# quad_l293d.net
KiCad netlist of a schematic drawn in EAGLE
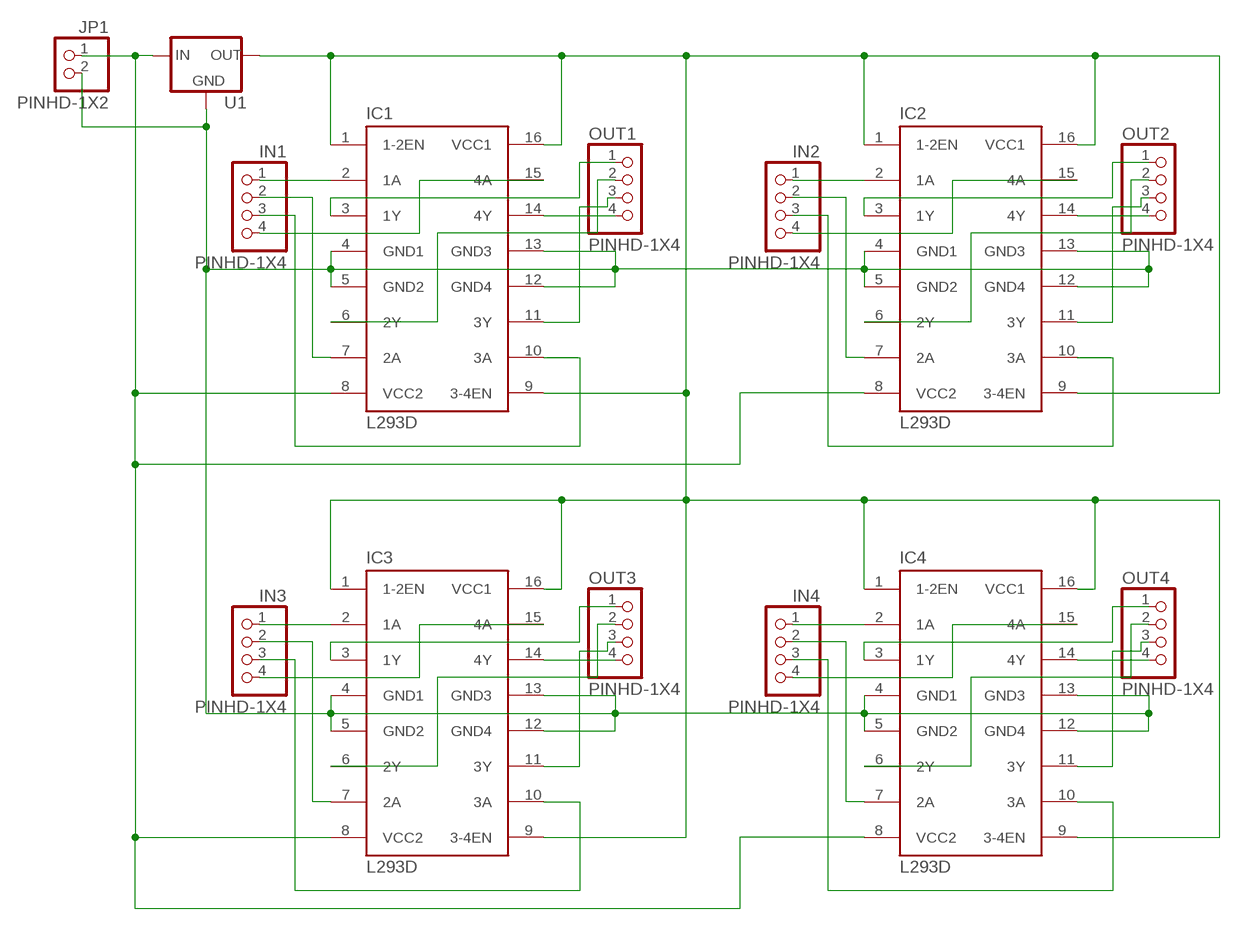
[diagram p0: schematic, sheet 1]

(export (version "E")
  (design (tool "Eeschema 10.0.6"))
  (components
    (comp (ref "IC1")
      (value "L293D")
      (footprint "eagle-import:DIL16")
      (libsource (lib "eagle-import") (part "L293D"))
    )
    (comp (ref "IC2")
      (value "L293D")
      (footprint "eagle-import:DIL16")
      (libsource (lib "eagle-import") (part "L293D"))
    )
    (comp (ref "IC3")
      (value "L293D")
      (footprint "eagle-import:DIL16")
      (libsource (lib "eagle-import") (part "L293D"))
    )
    (comp (ref "IC4")
      (value "L293D")
      (footprint "eagle-import:DIL16")
      (libsource (lib "eagle-import") (part "L293D"))
    )
    (comp (ref "IN1")
      (value "PINHD-1X4")
      (footprint "eagle-import:1X04")
      (libsource (lib "eagle-import") (part "PINHD-1X4"))
    )
    (comp (ref "IN2")
      (value "PINHD-1X4")
      (footprint "eagle-import:1X04")
      (libsource (lib "eagle-import") (part "PINHD-1X4"))
    )
    (comp (ref "IN3")
      (value "PINHD-1X4")
      (footprint "eagle-import:1X04")
      (libsource (lib "eagle-import") (part "PINHD-1X4"))
    )
    (comp (ref "IN4")
      (value "PINHD-1X4")
      (footprint "eagle-import:1X04")
      (libsource (lib "eagle-import") (part "PINHD-1X4"))
    )
    (comp (ref "JP1")
      (value "PINHD-1X2")
      (footprint "eagle-import:1X02")
      (libsource (lib "eagle-import") (part "PINHD-1X2"))
    )
    (comp (ref "OUT1")
      (value "PINHD-1X4")
      (footprint "eagle-import:1X04")
      (libsource (lib "eagle-import") (part "PINHD-1X4"))
    )
    (comp (ref "OUT2")
      (value "PINHD-1X4")
      (footprint "eagle-import:1X04")
      (libsource (lib "eagle-import") (part "PINHD-1X4"))
    )
    (comp (ref "OUT3")
      (value "PINHD-1X4")
      (footprint "eagle-import:1X04")
      (libsource (lib "eagle-import") (part "PINHD-1X4"))
    )
    (comp (ref "OUT4")
      (value "PINHD-1X4")
      (footprint "eagle-import:1X04")
      (libsource (lib "eagle-import") (part "PINHD-1X4"))
    )
    (comp (ref "U1")
      (value "V_REG_78XX-TO-220")
      (footprint "eagle-import:TO-220-ALT")
      (libsource (lib "eagle-import") (part "V_REG_78XX-TO-220"))
    )
  )
  (nets
    (net (code "1") (name "Net-(IC1-1-2EN)") (class "Default")
      (node (ref "IC1") (pin "1") (pinfunction "1-2EN_1") (pintype "input"))
      (node (ref "IC1") (pin "16") (pinfunction "VCC1_16") (pintype "power_in"))
      (node (ref "IC1") (pin "9") (pinfunction "3-4EN_9") (pintype "input"))
      (node (ref "IC2") (pin "1") (pinfunction "1-2EN_1") (pintype "input"))
      (node (ref "IC2") (pin "16") (pinfunction "VCC1_16") (pintype "power_in"))
      (node (ref "IC2") (pin "9") (pinfunction "3-4EN_9") (pintype "input"))
      (node (ref "IC3") (pin "1") (pinfunction "1-2EN_1") (pintype "input"))
      (node (ref "IC3") (pin "16") (pinfunction "VCC1_16") (pintype "power_in"))
      (node (ref "IC3") (pin "9") (pinfunction "3-4EN_9") (pintype "input"))
      (node (ref "IC4") (pin "1") (pinfunction "1-2EN_1") (pintype "input"))
      (node (ref "IC4") (pin "16") (pinfunction "VCC1_16") (pintype "power_in"))
      (node (ref "IC4") (pin "9") (pinfunction "3-4EN_9") (pintype "input"))
      (node (ref "U1") (pin "OUT") (pinfunction "OUT_OUT") (pintype "passive"))
    )
    (net (code "2") (name "Net-(IC1-1A)") (class "Default")
      (node (ref "IC1") (pin "2") (pinfunction "1A_2") (pintype "input"))
      (node (ref "IN1") (pin "1") (pinfunction "1_1") (pintype "passive"))
    )
    (net (code "3") (name "Net-(IC1-1Y)") (class "Default")
      (node (ref "IC1") (pin "3") (pinfunction "1Y_3") (pintype "output"))
      (node (ref "OUT1") (pin "1") (pinfunction "1_1") (pintype "passive"))
    )
    (net (code "4") (name "Net-(IC1-2A)") (class "Default")
      (node (ref "IC1") (pin "7") (pinfunction "2A_7") (pintype "input"))
      (node (ref "IN1") (pin "2") (pinfunction "2_2") (pintype "passive"))
    )
    (net (code "5") (name "Net-(IC1-2Y)") (class "Default")
      (node (ref "IC1") (pin "6") (pinfunction "2Y_6") (pintype "output"))
      (node (ref "OUT1") (pin "2") (pinfunction "2_2") (pintype "passive"))
    )
    (net (code "6") (name "Net-(IC1-3A)") (class "Default")
      (node (ref "IC1") (pin "10") (pinfunction "3A_10") (pintype "input"))
      (node (ref "IN1") (pin "3") (pinfunction "3_3") (pintype "passive"))
    )
    (net (code "7") (name "Net-(IC1-3Y)") (class "Default")
      (node (ref "IC1") (pin "11") (pinfunction "3Y_11") (pintype "output"))
      (node (ref "OUT1") (pin "3") (pinfunction "3_3") (pintype "passive"))
    )
    (net (code "8") (name "Net-(IC1-4A)") (class "Default")
      (node (ref "IC1") (pin "15") (pinfunction "4A_15") (pintype "input"))
      (node (ref "IN1") (pin "4") (pinfunction "4_4") (pintype "passive"))
    )
    (net (code "9") (name "Net-(IC1-4Y)") (class "Default")
      (node (ref "IC1") (pin "14") (pinfunction "4Y_14") (pintype "output"))
      (node (ref "OUT1") (pin "4") (pinfunction "4_4") (pintype "passive"))
    )
    (net (code "10") (name "Net-(IC1-GND1)") (class "Default")
      (node (ref "IC1") (pin "12") (pinfunction "GND4_12") (pintype "power_in"))
      (node (ref "IC1") (pin "13") (pinfunction "GND3_13") (pintype "power_in"))
      (node (ref "IC1") (pin "4") (pinfunction "GND1_4") (pintype "power_in"))
      (node (ref "IC1") (pin "5") (pinfunction "GND2_5") (pintype "power_in"))
      (node (ref "IC2") (pin "12") (pinfunction "GND4_12") (pintype "power_in"))
      (node (ref "IC2") (pin "13") (pinfunction "GND3_13") (pintype "power_in"))
      (node (ref "IC2") (pin "4") (pinfunction "GND1_4") (pintype "power_in"))
      (node (ref "IC2") (pin "5") (pinfunction "GND2_5") (pintype "power_in"))
      (node (ref "IC3") (pin "12") (pinfunction "GND4_12") (pintype "power_in"))
      (node (ref "IC3") (pin "13") (pinfunction "GND3_13") (pintype "power_in"))
      (node (ref "IC3") (pin "4") (pinfunction "GND1_4") (pintype "power_in"))
      (node (ref "IC3") (pin "5") (pinfunction "GND2_5") (pintype "power_in"))
      (node (ref "IC4") (pin "12") (pinfunction "GND4_12") (pintype "power_in"))
      (node (ref "IC4") (pin "13") (pinfunction "GND3_13") (pintype "power_in"))
      (node (ref "IC4") (pin "4") (pinfunction "GND1_4") (pintype "power_in"))
      (node (ref "IC4") (pin "5") (pinfunction "GND2_5") (pintype "power_in"))
      (node (ref "JP1") (pin "2") (pinfunction "2_2") (pintype "passive"))
      (node (ref "U1") (pin "GND") (pinfunction "GND_GND") (pintype "input"))
    )
    (net (code "11") (name "Net-(IC1-VCC2)") (class "Default")
      (node (ref "IC1") (pin "8") (pinfunction "VCC2_8") (pintype "power_in"))
      (node (ref "IC2") (pin "8") (pinfunction "VCC2_8") (pintype "power_in"))
      (node (ref "IC3") (pin "8") (pinfunction "VCC2_8") (pintype "power_in"))
      (node (ref "IC4") (pin "8") (pinfunction "VCC2_8") (pintype "power_in"))
      (node (ref "JP1") (pin "1") (pinfunction "1_1") (pintype "passive"))
      (node (ref "U1") (pin "IN") (pinfunction "IN_IN") (pintype "input"))
    )
    (net (code "12") (name "Net-(IC2-1A)") (class "Default")
      (node (ref "IC2") (pin "2") (pinfunction "1A_2") (pintype "input"))
      (node (ref "IN2") (pin "1") (pinfunction "1_1") (pintype "passive"))
    )
    (net (code "13") (name "Net-(IC2-1Y)") (class "Default")
      (node (ref "IC2") (pin "3") (pinfunction "1Y_3") (pintype "output"))
      (node (ref "OUT2") (pin "1") (pinfunction "1_1") (pintype "passive"))
    )
    (net (code "14") (name "Net-(IC2-2A)") (class "Default")
      (node (ref "IC2") (pin "7") (pinfunction "2A_7") (pintype "input"))
      (node (ref "IN2") (pin "2") (pinfunction "2_2") (pintype "passive"))
    )
    (net (code "15") (name "Net-(IC2-2Y)") (class "Default")
      (node (ref "IC2") (pin "6") (pinfunction "2Y_6") (pintype "output"))
      (node (ref "OUT2") (pin "2") (pinfunction "2_2") (pintype "passive"))
    )
    (net (code "16") (name "Net-(IC2-3A)") (class "Default")
      (node (ref "IC2") (pin "10") (pinfunction "3A_10") (pintype "input"))
      (node (ref "IN2") (pin "3") (pinfunction "3_3") (pintype "passive"))
    )
    (net (code "17") (name "Net-(IC2-3Y)") (class "Default")
      (node (ref "IC2") (pin "11") (pinfunction "3Y_11") (pintype "output"))
      (node (ref "OUT2") (pin "3") (pinfunction "3_3") (pintype "passive"))
    )
    (net (code "18") (name "Net-(IC2-4A)") (class "Default")
      (node (ref "IC2") (pin "15") (pinfunction "4A_15") (pintype "input"))
      (node (ref "IN2") (pin "4") (pinfunction "4_4") (pintype "passive"))
    )
    (net (code "19") (name "Net-(IC2-4Y)") (class "Default")
      (node (ref "IC2") (pin "14") (pinfunction "4Y_14") (pintype "output"))
      (node (ref "OUT2") (pin "4") (pinfunction "4_4") (pintype "passive"))
    )
    (net (code "20") (name "Net-(IC3-1A)") (class "Default")
      (node (ref "IC3") (pin "2") (pinfunction "1A_2") (pintype "input"))
      (node (ref "IN3") (pin "1") (pinfunction "1_1") (pintype "passive"))
    )
    (net (code "21") (name "Net-(IC3-1Y)") (class "Default")
      (node (ref "IC3") (pin "3") (pinfunction "1Y_3") (pintype "output"))
      (node (ref "OUT3") (pin "1") (pinfunction "1_1") (pintype "passive"))
    )
    (net (code "22") (name "Net-(IC3-2A)") (class "Default")
      (node (ref "IC3") (pin "7") (pinfunction "2A_7") (pintype "input"))
      (node (ref "IN3") (pin "2") (pinfunction "2_2") (pintype "passive"))
    )
    (net (code "23") (name "Net-(IC3-2Y)") (class "Default")
      (node (ref "IC3") (pin "6") (pinfunction "2Y_6") (pintype "output"))
      (node (ref "OUT3") (pin "2") (pinfunction "2_2") (pintype "passive"))
    )
    (net (code "24") (name "Net-(IC3-3A)") (class "Default")
      (node (ref "IC3") (pin "10") (pinfunction "3A_10") (pintype "input"))
      (node (ref "IN3") (pin "3") (pinfunction "3_3") (pintype "passive"))
    )
    (net (code "25") (name "Net-(IC3-3Y)") (class "Default")
      (node (ref "IC3") (pin "11") (pinfunction "3Y_11") (pintype "output"))
      (node (ref "OUT3") (pin "3") (pinfunction "3_3") (pintype "passive"))
    )
    (net (code "26") (name "Net-(IC3-4A)") (class "Default")
      (node (ref "IC3") (pin "15") (pinfunction "4A_15") (pintype "input"))
      (node (ref "IN3") (pin "4") (pinfunction "4_4") (pintype "passive"))
    )
    (net (code "27") (name "Net-(IC3-4Y)") (class "Default")
      (node (ref "IC3") (pin "14") (pinfunction "4Y_14") (pintype "output"))
      (node (ref "OUT3") (pin "4") (pinfunction "4_4") (pintype "passive"))
    )
    (net (code "28") (name "Net-(IC4-1A)") (class "Default")
      (node (ref "IC4") (pin "2") (pinfunction "1A_2") (pintype "input"))
      (node (ref "IN4") (pin "1") (pinfunction "1_1") (pintype "passive"))
    )
    (net (code "29") (name "Net-(IC4-1Y)") (class "Default")
      (node (ref "IC4") (pin "3") (pinfunction "1Y_3") (pintype "output"))
      (node (ref "OUT4") (pin "1") (pinfunction "1_1") (pintype "passive"))
    )
    (net (code "30") (name "Net-(IC4-2A)") (class "Default")
      (node (ref "IC4") (pin "7") (pinfunction "2A_7") (pintype "input"))
      (node (ref "IN4") (pin "2") (pinfunction "2_2") (pintype "passive"))
    )
    (net (code "31") (name "Net-(IC4-2Y)") (class "Default")
      (node (ref "IC4") (pin "6") (pinfunction "2Y_6") (pintype "output"))
      (node (ref "OUT4") (pin "2") (pinfunction "2_2") (pintype "passive"))
    )
    (net (code "32") (name "Net-(IC4-3A)") (class "Default")
      (node (ref "IC4") (pin "10") (pinfunction "3A_10") (pintype "input"))
      (node (ref "IN4") (pin "3") (pinfunction "3_3") (pintype "passive"))
    )
    (net (code "33") (name "Net-(IC4-3Y)") (class "Default")
      (node (ref "IC4") (pin "11") (pinfunction "3Y_11") (pintype "output"))
      (node (ref "OUT4") (pin "3") (pinfunction "3_3") (pintype "passive"))
    )
    (net (code "34") (name "Net-(IC4-4A)") (class "Default")
      (node (ref "IC4") (pin "15") (pinfunction "4A_15") (pintype "input"))
      (node (ref "IN4") (pin "4") (pinfunction "4_4") (pintype "passive"))
    )
    (net (code "35") (name "Net-(IC4-4Y)") (class "Default")
      (node (ref "IC4") (pin "14") (pinfunction "4Y_14") (pintype "output"))
      (node (ref "OUT4") (pin "4") (pinfunction "4_4") (pintype "passive"))
    )
  )
)
